# Adafruit_2_8_inch_TFT_w_Capacitive_Touch.net
KiCad netlist of a schematic drawn in EAGLE
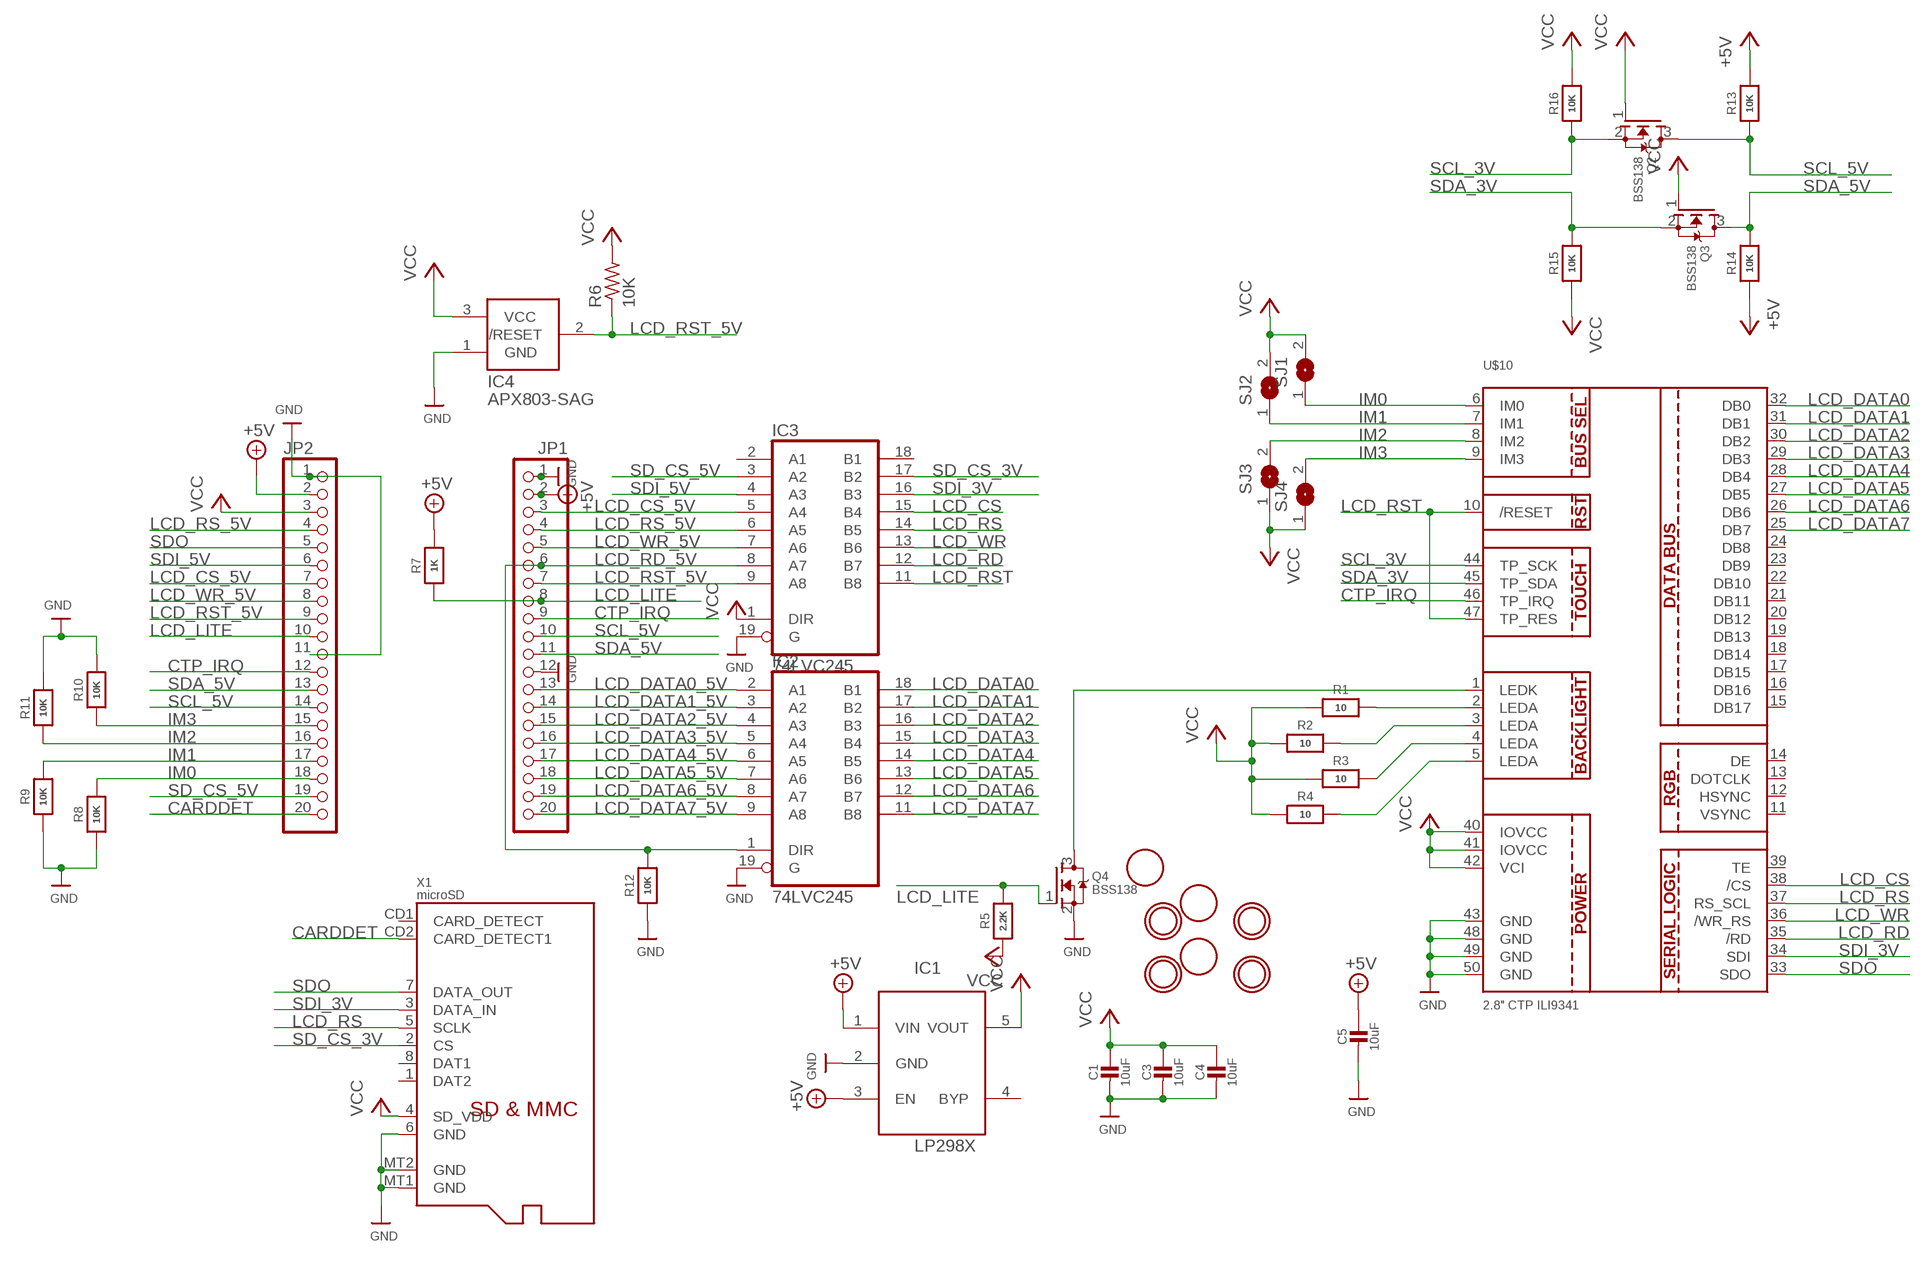
[diagram p0: schematic, sheet 1]

(export (version "E")
  (design (tool "Eeschema 10.0.6"))
  (components
    (comp (ref "C1")
      (value "10uF")
      (footprint "eagle-import:0805-NO")
      (libsource (lib "eagle-import") (part "CAP_CERAMIC0805-NOOUTLINE"))
    )
    (comp (ref "C3")
      (value "10uF")
      (footprint "eagle-import:0805-NO")
      (libsource (lib "eagle-import") (part "CAP_CERAMIC0805-NOOUTLINE"))
    )
    (comp (ref "C4")
      (value "10uF")
      (footprint "eagle-import:0805-NO")
      (libsource (lib "eagle-import") (part "CAP_CERAMIC0805-NOOUTLINE"))
    )
    (comp (ref "C5")
      (value "10uF")
      (footprint "eagle-import:0805-NO")
      (libsource (lib "eagle-import") (part "CAP_CERAMIC0805-NOOUTLINE"))
    )
    (comp (ref "IC1")
      (value "MIC5225-3.3")
      (footprint "eagle-import:SOT23-5L")
      (libsource (lib "eagle-import") (part "LP298XS"))
    )
    (comp (ref "IC2")
      (value "74LVC245")
      (footprint "eagle-import:SO20W")
      (libsource (lib "eagle-import") (part "74245DWACT"))
    )
    (comp (ref "IC3")
      (value "74LVC245")
      (footprint "eagle-import:SO20W")
      (libsource (lib "eagle-import") (part "74245DWACT"))
    )
    (comp (ref "IC4")
      (value "APX803-SAG")
      (footprint "eagle-import:SOT23")
      (libsource (lib "eagle-import") (part "AXP083-SAG"))
    )
    (comp (ref "JP1")
      (value "HEADER-1X20ROUND")
      (footprint "eagle-import:1X20_ROUND")
      (libsource (lib "eagle-import") (part "HEADER-1X20ROUND"))
    )
    (comp (ref "JP2")
      (value "HEADER-1X20ROUND")
      (footprint "eagle-import:1X20_ROUND")
      (libsource (lib "eagle-import") (part "HEADER-1X20ROUND"))
    )
    (comp (ref "Q2")
      (value "BSS138")
      (footprint "eagle-import:SOT23-WIDE")
      (libsource (lib "eagle-import") (part "MOSFET-NWIDE"))
    )
    (comp (ref "Q3")
      (value "BSS138")
      (footprint "eagle-import:SOT23-WIDE")
      (libsource (lib "eagle-import") (part "MOSFET-NWIDE"))
    )
    (comp (ref "Q4")
      (value "BSS138")
      (footprint "eagle-import:SOT23-WIDE")
      (libsource (lib "eagle-import") (part "MOSFET-NWIDE"))
    )
    (comp (ref "R1")
      (value "10")
      (footprint "eagle-import:0805-NO")
      (libsource (lib "eagle-import") (part "RESISTOR0805_NOOUTLINE"))
    )
    (comp (ref "R2")
      (value "10")
      (footprint "eagle-import:0805-NO")
      (libsource (lib "eagle-import") (part "RESISTOR0805_NOOUTLINE"))
    )
    (comp (ref "R3")
      (value "10")
      (footprint "eagle-import:0805-NO")
      (libsource (lib "eagle-import") (part "RESISTOR0805_NOOUTLINE"))
    )
    (comp (ref "R4")
      (value "10")
      (footprint "eagle-import:0805-NO")
      (libsource (lib "eagle-import") (part "RESISTOR0805_NOOUTLINE"))
    )
    (comp (ref "R5")
      (value "2.2K")
      (footprint "eagle-import:0805-NO")
      (libsource (lib "eagle-import") (part "RESISTOR0805_NOOUTLINE"))
    )
    (comp (ref "R6")
      (value "10K")
      (footprint "eagle-import:R0805")
      (libsource (lib "eagle-import") (part "R-US_R0805"))
    )
    (comp (ref "R7")
      (value "1K")
      (footprint "eagle-import:0805-NO")
      (libsource (lib "eagle-import") (part "RESISTOR0805_NOOUTLINE"))
    )
    (comp (ref "R8")
      (value "10K")
      (footprint "eagle-import:0805-NO")
      (libsource (lib "eagle-import") (part "RESISTOR0805_NOOUTLINE"))
    )
    (comp (ref "R9")
      (value "10K")
      (footprint "eagle-import:0805-NO")
      (libsource (lib "eagle-import") (part "RESISTOR0805_NOOUTLINE"))
    )
    (comp (ref "R10")
      (value "10K")
      (footprint "eagle-import:0805-NO")
      (libsource (lib "eagle-import") (part "RESISTOR0805_NOOUTLINE"))
    )
    (comp (ref "R11")
      (value "10K")
      (footprint "eagle-import:0805-NO")
      (libsource (lib "eagle-import") (part "RESISTOR0805_NOOUTLINE"))
    )
    (comp (ref "R12")
      (value "10K")
      (footprint "eagle-import:0805-NO")
      (libsource (lib "eagle-import") (part "RESISTOR0805_NOOUTLINE"))
    )
    (comp (ref "R13")
      (value "10K")
      (footprint "eagle-import:0805-NO")
      (libsource (lib "eagle-import") (part "RESISTOR0805_NOOUTLINE"))
    )
    (comp (ref "R14")
      (value "10K")
      (footprint "eagle-import:0805-NO")
      (libsource (lib "eagle-import") (part "RESISTOR0805_NOOUTLINE"))
    )
    (comp (ref "R15")
      (value "10K")
      (footprint "eagle-import:0805-NO")
      (libsource (lib "eagle-import") (part "RESISTOR0805_NOOUTLINE"))
    )
    (comp (ref "R16")
      (value "10K")
      (footprint "eagle-import:0805-NO")
      (libsource (lib "eagle-import") (part "RESISTOR0805_NOOUTLINE"))
    )
    (comp (ref "SJ1")
      (value "SOLDERJUMPER")
      (footprint "eagle-import:SOLDERJUMPER_ARROW_NOPASTE")
      (libsource (lib "eagle-import") (part "SOLDERJUMPER"))
    )
    (comp (ref "SJ2")
      (value "SOLDERJUMPER")
      (footprint "eagle-import:SOLDERJUMPER_ARROW_NOPASTE")
      (libsource (lib "eagle-import") (part "SOLDERJUMPER"))
    )
    (comp (ref "SJ3")
      (value "SOLDERJUMPER")
      (footprint "eagle-import:SOLDERJUMPER_ARROW_NOPASTE")
      (libsource (lib "eagle-import") (part "SOLDERJUMPER"))
    )
    (comp (ref "SJ4")
      (value "SOLDERJUMPER")
      (footprint "eagle-import:SOLDERJUMPER_ARROW_NOPASTE")
      (libsource (lib "eagle-import") (part "SOLDERJUMPER"))
    )
    (comp (ref "U$7")
      (value "MOUNTINGHOLE3.0THIN")
      (footprint "eagle-import:MOUNTINGHOLE_3.0_PLATEDTHIN")
      (libsource (lib "eagle-import") (part "MOUNTINGHOLE3.0THIN"))
    )
    (comp (ref "U$9")
      (value "FIDUCIAL")
      (footprint "eagle-import:FIDUCIAL_1MM")
      (libsource (lib "eagle-import") (part "FIDUCIAL"))
    )
    (comp (ref "U$10")
      (value "2.8\" CTP ILI9341")
      (footprint "eagle-import:TFT_2.83IN_240X320_50PIN")
      (libsource (lib "eagle-import") (part "DISP_LCD_CTP28_SAMPLE"))
    )
    (comp (ref "U$11")
      (value "FIDUCIAL")
      (footprint "eagle-import:FIDUCIAL_1MM")
      (libsource (lib "eagle-import") (part "FIDUCIAL"))
    )
    (comp (ref "U$15")
      (value "MOUNTINGHOLE3.0THIN")
      (footprint "eagle-import:MOUNTINGHOLE_3.0_PLATEDTHIN")
      (libsource (lib "eagle-import") (part "MOUNTINGHOLE3.0THIN"))
    )
    (comp (ref "U$16")
      (value "MOUNTINGHOLE3.0THIN")
      (footprint "eagle-import:MOUNTINGHOLE_3.0_PLATEDTHIN")
      (libsource (lib "eagle-import") (part "MOUNTINGHOLE3.0THIN"))
    )
    (comp (ref "U$17")
      (value "MOUNTINGHOLE3.0THIN")
      (footprint "eagle-import:MOUNTINGHOLE_3.0_PLATEDTHIN")
      (libsource (lib "eagle-import") (part "MOUNTINGHOLE3.0THIN"))
    )
    (comp (ref "U$23")
      (value "FIDUCIAL")
      (footprint "eagle-import:FIDUCIAL_1MM")
      (libsource (lib "eagle-import") (part "FIDUCIAL"))
    )
    (comp (ref "X1")
      (value "microSD")
      (footprint "eagle-import:MICROSD")
      (libsource (lib "eagle-import") (part "MICROSD"))
    )
  )
  (nets
    (net (code "1") (name "+5V") (class "Default")
      (node (ref "C5") (pin "1") (pinfunction "1_1") (pintype "passive"))
      (node (ref "IC1") (pin "1") (pinfunction "VIN_1") (pintype "bidirectional"))
      (node (ref "IC1") (pin "3") (pinfunction "EN_3") (pintype "bidirectional"))
      (node (ref "JP1") (pin "2") (pinfunction "2_2") (pintype "passive"))
      (node (ref "JP2") (pin "2") (pinfunction "2_2") (pintype "passive"))
      (node (ref "R13") (pin "2") (pinfunction "2_2") (pintype "passive"))
      (node (ref "R14") (pin "1") (pinfunction "1_1") (pintype "passive"))
      (node (ref "R7") (pin "2") (pinfunction "2_2") (pintype "passive"))
    )
    (net (code "2") (name "/CARDDET") (class "Default")
      (node (ref "JP2") (pin "20") (pinfunction "20_20") (pintype "passive"))
      (node (ref "X1") (pin "CD2") (pinfunction "CARD_DETECT1_CD2") (pintype "passive"))
    )
    (net (code "3") (name "/CTP_IRQ") (class "Default")
      (node (ref "JP1") (pin "9") (pinfunction "9_9") (pintype "passive"))
      (node (ref "JP2") (pin "12") (pinfunction "12_12") (pintype "passive"))
      (node (ref "U$10") (pin "46") (pinfunction "TP_IRQ_46") (pintype "bidirectional"))
    )
    (net (code "4") (name "/IM0") (class "Default")
      (node (ref "JP2") (pin "18") (pinfunction "18_18") (pintype "passive"))
      (node (ref "R8") (pin "2") (pinfunction "2_2") (pintype "passive"))
      (node (ref "SJ1") (pin "1") (pinfunction "1_1") (pintype "passive"))
      (node (ref "U$10") (pin "6") (pinfunction "IM0_6") (pintype "bidirectional"))
    )
    (net (code "5") (name "/IM1") (class "Default")
      (node (ref "JP2") (pin "17") (pinfunction "17_17") (pintype "passive"))
      (node (ref "R9") (pin "2") (pinfunction "2_2") (pintype "passive"))
      (node (ref "SJ2") (pin "1") (pinfunction "1_1") (pintype "passive"))
      (node (ref "U$10") (pin "7") (pinfunction "IM1_7") (pintype "bidirectional"))
    )
    (net (code "6") (name "/IM2") (class "Default")
      (node (ref "JP2") (pin "16") (pinfunction "16_16") (pintype "passive"))
      (node (ref "R11") (pin "1") (pinfunction "1_1") (pintype "passive"))
      (node (ref "SJ3") (pin "2") (pinfunction "2_2") (pintype "passive"))
      (node (ref "U$10") (pin "8") (pinfunction "IM2_8") (pintype "bidirectional"))
    )
    (net (code "7") (name "/IM3") (class "Default")
      (node (ref "JP2") (pin "15") (pinfunction "15_15") (pintype "passive"))
      (node (ref "R10") (pin "1") (pinfunction "1_1") (pintype "passive"))
      (node (ref "SJ4") (pin "2") (pinfunction "2_2") (pintype "passive"))
      (node (ref "U$10") (pin "9") (pinfunction "IM3_9") (pintype "bidirectional"))
    )
    (net (code "8") (name "/LCD_CS") (class "Default")
      (node (ref "IC3") (pin "15") (pinfunction "B4_15") (pintype "bidirectional"))
      (node (ref "U$10") (pin "38") (pinfunction "/CS_38") (pintype "bidirectional"))
    )
    (net (code "9") (name "/LCD_CS_5V") (class "Default")
      (node (ref "IC3") (pin "5") (pinfunction "A4_5") (pintype "bidirectional"))
      (node (ref "JP1") (pin "3") (pinfunction "3_3") (pintype "passive"))
      (node (ref "JP2") (pin "7") (pinfunction "7_7") (pintype "passive"))
    )
    (net (code "10") (name "/LCD_DATA0") (class "Default")
      (node (ref "IC2") (pin "18") (pinfunction "B1_18") (pintype "bidirectional"))
      (node (ref "U$10") (pin "32") (pinfunction "DB0_32") (pintype "bidirectional"))
    )
    (net (code "11") (name "/LCD_DATA0_5V") (class "Default")
      (node (ref "IC2") (pin "2") (pinfunction "A1_2") (pintype "bidirectional"))
      (node (ref "JP1") (pin "13") (pinfunction "13_13") (pintype "passive"))
    )
    (net (code "12") (name "/LCD_DATA1") (class "Default")
      (node (ref "IC2") (pin "17") (pinfunction "B2_17") (pintype "bidirectional"))
      (node (ref "U$10") (pin "31") (pinfunction "DB1_31") (pintype "bidirectional"))
    )
    (net (code "13") (name "/LCD_DATA1_5V") (class "Default")
      (node (ref "IC2") (pin "3") (pinfunction "A2_3") (pintype "bidirectional"))
      (node (ref "JP1") (pin "14") (pinfunction "14_14") (pintype "passive"))
    )
    (net (code "14") (name "/LCD_DATA2") (class "Default")
      (node (ref "IC2") (pin "16") (pinfunction "B3_16") (pintype "bidirectional"))
      (node (ref "U$10") (pin "30") (pinfunction "DB2_30") (pintype "bidirectional"))
    )
    (net (code "15") (name "/LCD_DATA2_5V") (class "Default")
      (node (ref "IC2") (pin "4") (pinfunction "A3_4") (pintype "bidirectional"))
      (node (ref "JP1") (pin "15") (pinfunction "15_15") (pintype "passive"))
    )
    (net (code "16") (name "/LCD_DATA3") (class "Default")
      (node (ref "IC2") (pin "15") (pinfunction "B4_15") (pintype "bidirectional"))
      (node (ref "U$10") (pin "29") (pinfunction "DB3_29") (pintype "bidirectional"))
    )
    (net (code "17") (name "/LCD_DATA3_5V") (class "Default")
      (node (ref "IC2") (pin "5") (pinfunction "A4_5") (pintype "bidirectional"))
      (node (ref "JP1") (pin "16") (pinfunction "16_16") (pintype "passive"))
    )
    (net (code "18") (name "/LCD_DATA4") (class "Default")
      (node (ref "IC2") (pin "14") (pinfunction "B5_14") (pintype "bidirectional"))
      (node (ref "U$10") (pin "28") (pinfunction "DB4_28") (pintype "bidirectional"))
    )
    (net (code "19") (name "/LCD_DATA4_5V") (class "Default")
      (node (ref "IC2") (pin "6") (pinfunction "A5_6") (pintype "bidirectional"))
      (node (ref "JP1") (pin "17") (pinfunction "17_17") (pintype "passive"))
    )
    (net (code "20") (name "/LCD_DATA5") (class "Default")
      (node (ref "IC2") (pin "13") (pinfunction "B6_13") (pintype "bidirectional"))
      (node (ref "U$10") (pin "27") (pinfunction "DB5_27") (pintype "bidirectional"))
    )
    (net (code "21") (name "/LCD_DATA5_5V") (class "Default")
      (node (ref "IC2") (pin "7") (pinfunction "A6_7") (pintype "bidirectional"))
      (node (ref "JP1") (pin "18") (pinfunction "18_18") (pintype "passive"))
    )
    (net (code "22") (name "/LCD_DATA6") (class "Default")
      (node (ref "IC2") (pin "12") (pinfunction "B7_12") (pintype "bidirectional"))
      (node (ref "U$10") (pin "26") (pinfunction "DB6_26") (pintype "bidirectional"))
    )
    (net (code "23") (name "/LCD_DATA6_5V") (class "Default")
      (node (ref "IC2") (pin "8") (pinfunction "A7_8") (pintype "bidirectional"))
      (node (ref "JP1") (pin "19") (pinfunction "19_19") (pintype "passive"))
    )
    (net (code "24") (name "/LCD_DATA7") (class "Default")
      (node (ref "IC2") (pin "11") (pinfunction "B8_11") (pintype "bidirectional"))
      (node (ref "U$10") (pin "25") (pinfunction "DB7_25") (pintype "bidirectional"))
    )
    (net (code "25") (name "/LCD_DATA7_5V") (class "Default")
      (node (ref "IC2") (pin "9") (pinfunction "A8_9") (pintype "bidirectional"))
      (node (ref "JP1") (pin "20") (pinfunction "20_20") (pintype "passive"))
    )
    (net (code "26") (name "/LCD_LITE") (class "Default")
      (node (ref "JP1") (pin "8") (pinfunction "8_8") (pintype "passive"))
      (node (ref "JP2") (pin "10") (pinfunction "10_10") (pintype "passive"))
      (node (ref "Q4") (pin "1") (pinfunction "G_1") (pintype "bidirectional"))
      (node (ref "R5") (pin "2") (pinfunction "2_2") (pintype "passive"))
      (node (ref "R7") (pin "1") (pinfunction "1_1") (pintype "passive"))
    )
    (net (code "27") (name "/LCD_RD") (class "Default")
      (node (ref "IC3") (pin "12") (pinfunction "B7_12") (pintype "bidirectional"))
      (node (ref "U$10") (pin "35") (pinfunction "/RD_35") (pintype "bidirectional"))
    )
    (net (code "28") (name "/LCD_RD_5V") (class "Default")
      (node (ref "IC2") (pin "1") (pinfunction "DIR_1") (pintype "input"))
      (node (ref "IC3") (pin "8") (pinfunction "A7_8") (pintype "bidirectional"))
      (node (ref "JP1") (pin "6") (pinfunction "6_6") (pintype "passive"))
      (node (ref "R12") (pin "2") (pinfunction "2_2") (pintype "passive"))
    )
    (net (code "29") (name "/LCD_RS") (class "Default")
      (node (ref "IC3") (pin "14") (pinfunction "B5_14") (pintype "bidirectional"))
      (node (ref "U$10") (pin "37") (pinfunction "RS_SCL_37") (pintype "bidirectional"))
      (node (ref "X1") (pin "5") (pinfunction "SCLK_5") (pintype "input"))
    )
    (net (code "30") (name "/LCD_RST") (class "Default")
      (node (ref "IC3") (pin "11") (pinfunction "B8_11") (pintype "bidirectional"))
      (node (ref "U$10") (pin "10") (pinfunction "/RESET_10") (pintype "bidirectional"))
      (node (ref "U$10") (pin "47") (pinfunction "TP_RES_47") (pintype "bidirectional"))
    )
    (net (code "31") (name "/LCD_RST_5V") (class "Default")
      (node (ref "IC3") (pin "9") (pinfunction "A8_9") (pintype "bidirectional"))
      (node (ref "IC4") (pin "2") (pinfunction "/RESET_2") (pintype "output"))
      (node (ref "JP1") (pin "7") (pinfunction "7_7") (pintype "passive"))
      (node (ref "JP2") (pin "9") (pinfunction "9_9") (pintype "passive"))
      (node (ref "R6") (pin "1") (pinfunction "1_1") (pintype "passive"))
    )
    (net (code "32") (name "/LCD_RS_5V") (class "Default")
      (node (ref "IC3") (pin "6") (pinfunction "A5_6") (pintype "bidirectional"))
      (node (ref "JP1") (pin "4") (pinfunction "4_4") (pintype "passive"))
      (node (ref "JP2") (pin "4") (pinfunction "4_4") (pintype "passive"))
    )
    (net (code "33") (name "/LCD_WR") (class "Default")
      (node (ref "IC3") (pin "13") (pinfunction "B6_13") (pintype "bidirectional"))
      (node (ref "U$10") (pin "36") (pinfunction "/WR_RS_36") (pintype "bidirectional"))
    )
    (net (code "34") (name "/LCD_WR_5V") (class "Default")
      (node (ref "IC3") (pin "7") (pinfunction "A6_7") (pintype "bidirectional"))
      (node (ref "JP1") (pin "5") (pinfunction "5_5") (pintype "passive"))
      (node (ref "JP2") (pin "8") (pinfunction "8_8") (pintype "passive"))
    )
    (net (code "35") (name "/SCL_3V") (class "Default")
      (node (ref "Q2") (pin "2") (pinfunction "S_2") (pintype "bidirectional"))
      (node (ref "R16") (pin "1") (pinfunction "1_1") (pintype "passive"))
      (node (ref "U$10") (pin "44") (pinfunction "TP_SCK_44") (pintype "bidirectional"))
    )
    (net (code "36") (name "/SCL_5V") (class "Default")
      (node (ref "JP1") (pin "10") (pinfunction "10_10") (pintype "passive"))
      (node (ref "JP2") (pin "14") (pinfunction "14_14") (pintype "passive"))
      (node (ref "Q2") (pin "3") (pinfunction "D_3") (pintype "bidirectional"))
      (node (ref "R13") (pin "1") (pinfunction "1_1") (pintype "passive"))
    )
    (net (code "37") (name "/SDA_3V") (class "Default")
      (node (ref "Q3") (pin "2") (pinfunction "S_2") (pintype "bidirectional"))
      (node (ref "R15") (pin "2") (pinfunction "2_2") (pintype "passive"))
      (node (ref "U$10") (pin "45") (pinfunction "TP_SDA_45") (pintype "bidirectional"))
    )
    (net (code "38") (name "/SDA_5V") (class "Default")
      (node (ref "JP1") (pin "11") (pinfunction "11_11") (pintype "passive"))
      (node (ref "JP2") (pin "13") (pinfunction "13_13") (pintype "passive"))
      (node (ref "Q3") (pin "3") (pinfunction "D_3") (pintype "bidirectional"))
      (node (ref "R14") (pin "2") (pinfunction "2_2") (pintype "passive"))
    )
    (net (code "39") (name "/SDI_3V") (class "Default")
      (node (ref "IC3") (pin "16") (pinfunction "B3_16") (pintype "bidirectional"))
      (node (ref "U$10") (pin "34") (pinfunction "SDI_34") (pintype "bidirectional"))
      (node (ref "X1") (pin "3") (pinfunction "DATA_IN_3") (pintype "input"))
    )
    (net (code "40") (name "/SDI_5V") (class "Default")
      (node (ref "IC3") (pin "4") (pinfunction "A3_4") (pintype "bidirectional"))
      (node (ref "JP2") (pin "6") (pinfunction "6_6") (pintype "passive"))
    )
    (net (code "41") (name "/SDO") (class "Default")
      (node (ref "JP2") (pin "5") (pinfunction "5_5") (pintype "passive"))
      (node (ref "U$10") (pin "33") (pinfunction "SDO_33") (pintype "bidirectional"))
      (node (ref "X1") (pin "7") (pinfunction "DATA_OUT_7") (pintype "output"))
    )
    (net (code "42") (name "/SD_CS_3V") (class "Default")
      (node (ref "IC3") (pin "17") (pinfunction "B2_17") (pintype "bidirectional"))
      (node (ref "X1") (pin "2") (pinfunction "CS_2") (pintype "input"))
    )
    (net (code "43") (name "/SD_CS_5V") (class "Default")
      (node (ref "IC3") (pin "3") (pinfunction "A2_3") (pintype "bidirectional"))
      (node (ref "JP2") (pin "19") (pinfunction "19_19") (pintype "passive"))
    )
    (net (code "44") (name "GND") (class "Default")
      (node (ref "C1") (pin "2") (pinfunction "2_2") (pintype "passive"))
      (node (ref "C3") (pin "2") (pinfunction "2_2") (pintype "passive"))
      (node (ref "C4") (pin "2") (pinfunction "2_2") (pintype "passive"))
      (node (ref "C5") (pin "2") (pinfunction "2_2") (pintype "passive"))
      (node (ref "IC1") (pin "2") (pinfunction "GND_2") (pintype "bidirectional"))
      (node (ref "IC2") (pin "19") (pinfunction "G_19") (pintype "input"))
      (node (ref "IC3") (pin "19") (pinfunction "G_19") (pintype "input"))
      (node (ref "IC4") (pin "1") (pinfunction "GND_1") (pintype "power_in"))
      (node (ref "JP1") (pin "1") (pinfunction "1_1") (pintype "passive"))
      (node (ref "JP1") (pin "12") (pinfunction "12_12") (pintype "passive"))
      (node (ref "JP2") (pin "1") (pinfunction "1_1") (pintype "passive"))
      (node (ref "JP2") (pin "11") (pinfunction "11_11") (pintype "passive"))
      (node (ref "Q4") (pin "2") (pinfunction "S_2") (pintype "bidirectional"))
      (node (ref "R10") (pin "2") (pinfunction "2_2") (pintype "passive"))
      (node (ref "R11") (pin "2") (pinfunction "2_2") (pintype "passive"))
      (node (ref "R12") (pin "1") (pinfunction "1_1") (pintype "passive"))
      (node (ref "R8") (pin "1") (pinfunction "1_1") (pintype "passive"))
      (node (ref "R9") (pin "1") (pinfunction "1_1") (pintype "passive"))
      (node (ref "U$10") (pin "43") (pinfunction "GND_43") (pintype "bidirectional"))
      (node (ref "U$10") (pin "48") (pinfunction "GND_48") (pintype "bidirectional"))
      (node (ref "U$10") (pin "49") (pinfunction "GND_49") (pintype "bidirectional"))
      (node (ref "U$10") (pin "50") (pinfunction "GND_50") (pintype "bidirectional"))
      (node (ref "X1") (pin "6") (pinfunction "GND_6") (pintype "power_in"))
      (node (ref "X1") (pin "MT1") (pinfunction "GND_MT1") (pintype "power_in"))
      (node (ref "X1") (pin "MT2") (pinfunction "GND_MT2") (pintype "power_in"))
    )
    (net (code "45") (name "Net-(Q4-D)") (class "Default")
      (node (ref "Q4") (pin "3") (pinfunction "D_3") (pintype "bidirectional"))
      (node (ref "U$10") (pin "1") (pinfunction "LEDK_1") (pintype "bidirectional"))
    )
    (net (code "46") (name "Net-(R1-Pad2)") (class "Default")
      (node (ref "R1") (pin "2") (pinfunction "2_2") (pintype "passive"))
      (node (ref "U$10") (pin "2") (pinfunction "LEDA_2") (pintype "bidirectional"))
    )
    (net (code "47") (name "Net-(R2-Pad2)") (class "Default")
      (node (ref "R2") (pin "2") (pinfunction "2_2") (pintype "passive"))
      (node (ref "U$10") (pin "3") (pinfunction "LEDA_3") (pintype "bidirectional"))
    )
    (net (code "48") (name "Net-(R3-Pad2)") (class "Default")
      (node (ref "R3") (pin "2") (pinfunction "2_2") (pintype "passive"))
      (node (ref "U$10") (pin "4") (pinfunction "LEDA_4") (pintype "bidirectional"))
    )
    (net (code "49") (name "Net-(R4-Pad2)") (class "Default")
      (node (ref "R4") (pin "2") (pinfunction "2_2") (pintype "passive"))
      (node (ref "U$10") (pin "5") (pinfunction "LEDA_5") (pintype "bidirectional"))
    )
    (net (code "50") (name "VCC") (class "Default")
      (node (ref "C1") (pin "1") (pinfunction "1_1") (pintype "passive"))
      (node (ref "C3") (pin "1") (pinfunction "1_1") (pintype "passive"))
      (node (ref "C4") (pin "1") (pinfunction "1_1") (pintype "passive"))
      (node (ref "IC1") (pin "5") (pinfunction "VOUT_5") (pintype "bidirectional"))
      (node (ref "IC3") (pin "1") (pinfunction "DIR_1") (pintype "input"))
      (node (ref "IC4") (pin "3") (pinfunction "VCC_3") (pintype "power_in"))
      (node (ref "JP2") (pin "3") (pinfunction "3_3") (pintype "passive"))
      (node (ref "Q2") (pin "1") (pinfunction "G_1") (pintype "bidirectional"))
      (node (ref "Q3") (pin "1") (pinfunction "G_1") (pintype "bidirectional"))
      (node (ref "R1") (pin "1") (pinfunction "1_1") (pintype "passive"))
      (node (ref "R15") (pin "1") (pinfunction "1_1") (pintype "passive"))
      (node (ref "R16") (pin "2") (pinfunction "2_2") (pintype "passive"))
      (node (ref "R2") (pin "1") (pinfunction "1_1") (pintype "passive"))
      (node (ref "R3") (pin "1") (pinfunction "1_1") (pintype "passive"))
      (node (ref "R4") (pin "1") (pinfunction "1_1") (pintype "passive"))
      (node (ref "R5") (pin "1") (pinfunction "1_1") (pintype "passive"))
      (node (ref "R6") (pin "2") (pinfunction "2_2") (pintype "passive"))
      (node (ref "SJ1") (pin "2") (pinfunction "2_2") (pintype "passive"))
      (node (ref "SJ2") (pin "2") (pinfunction "2_2") (pintype "passive"))
      (node (ref "SJ3") (pin "1") (pinfunction "1_1") (pintype "passive"))
      (node (ref "SJ4") (pin "1") (pinfunction "1_1") (pintype "passive"))
      (node (ref "U$10") (pin "40") (pinfunction "IOVCC_40") (pintype "bidirectional"))
      (node (ref "U$10") (pin "41") (pinfunction "IOVCC_41") (pintype "bidirectional"))
      (node (ref "U$10") (pin "42") (pinfunction "VCI_42") (pintype "bidirectional"))
      (node (ref "X1") (pin "4") (pinfunction "SD_VDD_4") (pintype "power_in"))
    )
    (net (code "51") (name "unconnected-(IC1-BYP-Pad4)") (class "Default")
      (node (ref "IC1") (pin "4") (pinfunction "BYP_4") (pintype "bidirectional"))
    )
    (net (code "52") (name "unconnected-(IC3A-A1-Pad2)") (class "Default")
      (node (ref "IC3") (pin "2") (pinfunction "A1_2") (pintype "bidirectional"))
    )
    (net (code "53") (name "unconnected-(IC3A-B1-Pad18)") (class "Default")
      (node (ref "IC3") (pin "18") (pinfunction "B1_18") (pintype "bidirectional"))
    )
    (net (code "54") (name "unconnected-(U$10-DB8-Pad24)") (class "Default")
      (node (ref "U$10") (pin "24") (pinfunction "DB8_24") (pintype "bidirectional"))
    )
    (net (code "55") (name "unconnected-(U$10-DB9-Pad23)") (class "Default")
      (node (ref "U$10") (pin "23") (pinfunction "DB9_23") (pintype "bidirectional"))
    )
    (net (code "56") (name "unconnected-(U$10-DB10-Pad22)") (class "Default")
      (node (ref "U$10") (pin "22") (pinfunction "DB10_22") (pintype "bidirectional"))
    )
    (net (code "57") (name "unconnected-(U$10-DB11-Pad21)") (class "Default")
      (node (ref "U$10") (pin "21") (pinfunction "DB11_21") (pintype "bidirectional"))
    )
    (net (code "58") (name "unconnected-(U$10-DB12-Pad20)") (class "Default")
      (node (ref "U$10") (pin "20") (pinfunction "DB12_20") (pintype "bidirectional"))
    )
    (net (code "59") (name "unconnected-(U$10-DB13-Pad19)") (class "Default")
      (node (ref "U$10") (pin "19") (pinfunction "DB13_19") (pintype "bidirectional"))
    )
    (net (code "60") (name "unconnected-(U$10-DB14-Pad18)") (class "Default")
      (node (ref "U$10") (pin "18") (pinfunction "DB14_18") (pintype "bidirectional"))
    )
    (net (code "61") (name "unconnected-(U$10-DB15-Pad17)") (class "Default")
      (node (ref "U$10") (pin "17") (pinfunction "DB15_17") (pintype "bidirectional"))
    )
    (net (code "62") (name "unconnected-(U$10-DB16-Pad16)") (class "Default")
      (node (ref "U$10") (pin "16") (pinfunction "DB16_16") (pintype "bidirectional"))
    )
    (net (code "63") (name "unconnected-(U$10-DB17-Pad15)") (class "Default")
      (node (ref "U$10") (pin "15") (pinfunction "DB17_15") (pintype "bidirectional"))
    )
    (net (code "64") (name "unconnected-(U$10-DE-Pad14)") (class "Default")
      (node (ref "U$10") (pin "14") (pinfunction "DE_14") (pintype "bidirectional"))
    )
    (net (code "65") (name "unconnected-(U$10-DOTCLK-Pad13)") (class "Default")
      (node (ref "U$10") (pin "13") (pinfunction "DOTCLK_13") (pintype "bidirectional"))
    )
    (net (code "66") (name "unconnected-(U$10-HSYNC-Pad12)") (class "Default")
      (node (ref "U$10") (pin "12") (pinfunction "HSYNC_12") (pintype "bidirectional"))
    )
    (net (code "67") (name "unconnected-(U$10-TE-Pad39)") (class "Default")
      (node (ref "U$10") (pin "39") (pinfunction "TE_39") (pintype "bidirectional"))
    )
    (net (code "68") (name "unconnected-(U$10-VSYNC-Pad11)") (class "Default")
      (node (ref "U$10") (pin "11") (pinfunction "VSYNC_11") (pintype "bidirectional"))
    )
    (net (code "69") (name "unconnected-(X1-CARD_DETECT-PadCD1)") (class "Default")
      (node (ref "X1") (pin "CD1") (pinfunction "CARD_DETECT_CD1") (pintype "passive"))
    )
    (net (code "70") (name "unconnected-(X1-DAT1-Pad8)") (class "Default")
      (node (ref "X1") (pin "8") (pinfunction "DAT1_8") (pintype "bidirectional"))
    )
    (net (code "71") (name "unconnected-(X1-DAT2-Pad1)") (class "Default")
      (node (ref "X1") (pin "1") (pinfunction "DAT2_1") (pintype "bidirectional"))
    )
  )
)
